# breakout.net
KiCad netlist of a schematic drawn in EAGLE
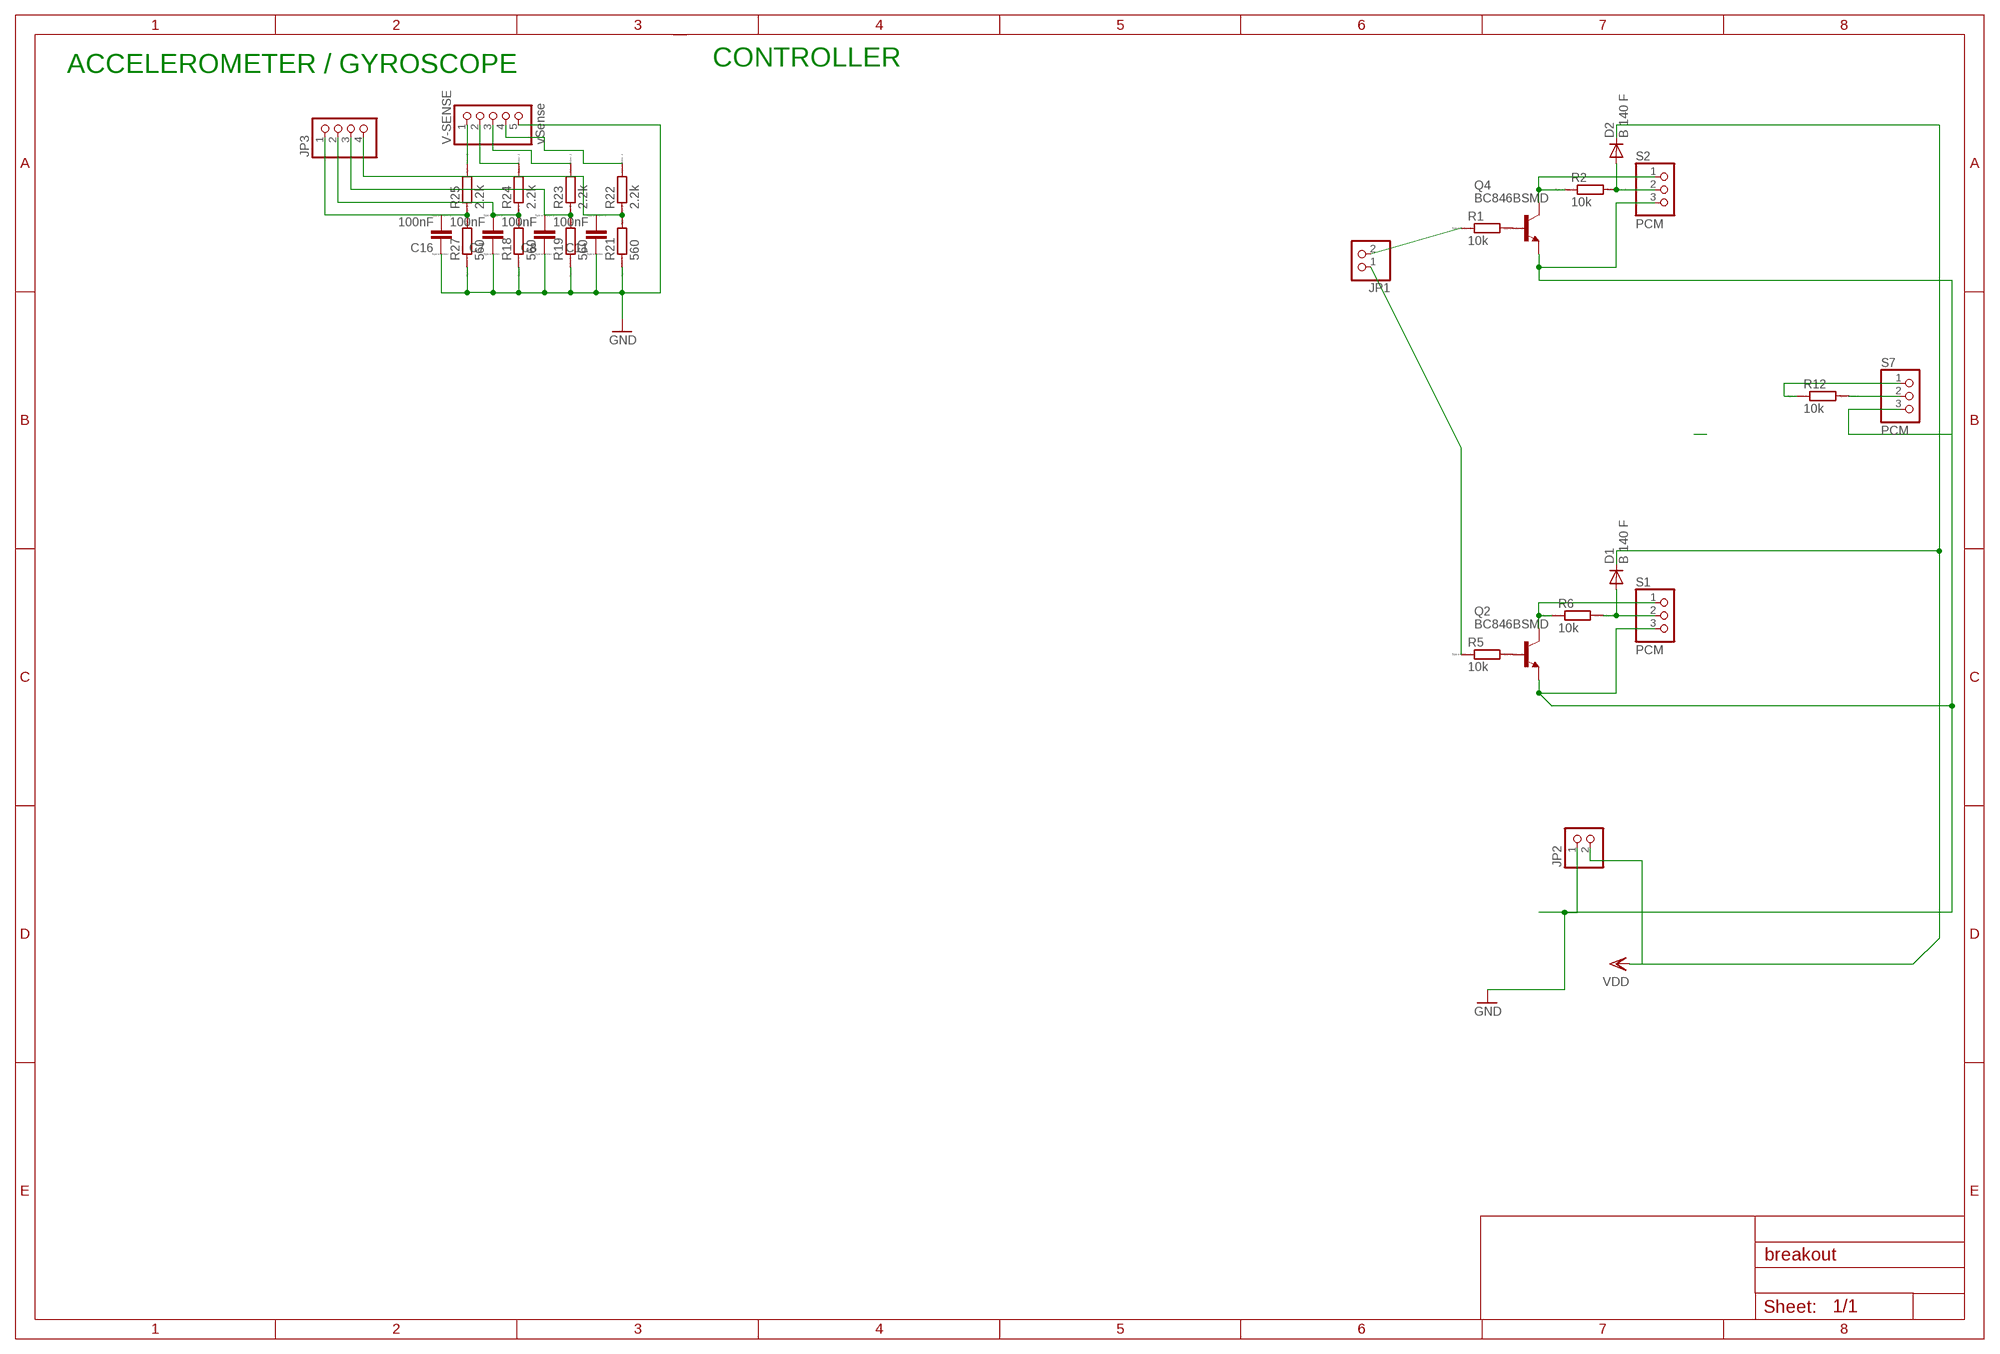
[diagram p0: schematic, sheet 1]

(export (version "E")
  (design (tool "Eeschema 10.0.6"))
  (components
    (comp (ref "C7")
      (value "100nF")
      (footprint "eagle-import:C0603")
      (libsource (lib "eagle-import") (part "CC0603"))
    )
    (comp (ref "C8")
      (value "100nF")
      (footprint "eagle-import:C0603")
      (libsource (lib "eagle-import") (part "CC0603"))
    )
    (comp (ref "C11")
      (value "100nF")
      (footprint "eagle-import:C0603")
      (libsource (lib "eagle-import") (part "CC0603"))
    )
    (comp (ref "C16")
      (value "100nF")
      (footprint "eagle-import:C0603")
      (libsource (lib "eagle-import") (part "CC0603"))
    )
    (comp (ref "D1")
      (value "B 140 F")
      (footprint "eagle-import:SOD-123_MINI-SMA")
      (libsource (lib "eagle-import") (part "CGRM400-G1"))
    )
    (comp (ref "D2")
      (value "B 140 F")
      (footprint "eagle-import:SOD-123_MINI-SMA")
      (libsource (lib "eagle-import") (part "CGRM400-G1"))
    )
    (comp (ref "JP1")
      (value "PINHD-1X2")
      (footprint "eagle-import:1X02")
      (libsource (lib "eagle-import") (part "PINHD-1X2"))
    )
    (comp (ref "JP2")
      (value "PINHD-1X2")
      (footprint "eagle-import:1X02")
      (libsource (lib "eagle-import") (part "PINHD-1X2"))
    )
    (comp (ref "JP3")
      (value "PINHD-1X4")
      (footprint "eagle-import:1X04")
      (libsource (lib "eagle-import") (part "PINHD-1X4"))
    )
    (comp (ref "Q2")
      (value "BC846BSMD")
      (footprint "eagle-import:SOT23")
      (libsource (lib "eagle-import") (part "BC846SMDB"))
    )
    (comp (ref "Q4")
      (value "BC846BSMD")
      (footprint "eagle-import:SOT23")
      (libsource (lib "eagle-import") (part "BC846SMDB"))
    )
    (comp (ref "R1")
      (value "10k")
      (footprint "eagle-import:R0603")
      (libsource (lib "eagle-import") (part "RR0603"))
    )
    (comp (ref "R2")
      (value "10k")
      (footprint "eagle-import:R0603")
      (libsource (lib "eagle-import") (part "RR0603"))
    )
    (comp (ref "R5")
      (value "10k")
      (footprint "eagle-import:R0603")
      (libsource (lib "eagle-import") (part "RR0603"))
    )
    (comp (ref "R6")
      (value "10k")
      (footprint "eagle-import:R0603")
      (libsource (lib "eagle-import") (part "RR0603"))
    )
    (comp (ref "R12")
      (value "10k")
      (footprint "eagle-import:R0603")
      (libsource (lib "eagle-import") (part "RR0603"))
    )
    (comp (ref "R18")
      (value "560")
      (footprint "eagle-import:R0603")
      (libsource (lib "eagle-import") (part "RR0603"))
    )
    (comp (ref "R19")
      (value "560")
      (footprint "eagle-import:R0603")
      (libsource (lib "eagle-import") (part "RR0603"))
    )
    (comp (ref "R21")
      (value "560")
      (footprint "eagle-import:R0603")
      (libsource (lib "eagle-import") (part "RR0603"))
    )
    (comp (ref "R22")
      (value "2.2k")
      (footprint "eagle-import:R0603")
      (libsource (lib "eagle-import") (part "RR0603"))
    )
    (comp (ref "R23")
      (value "2.2k")
      (footprint "eagle-import:R0603")
      (libsource (lib "eagle-import") (part "RR0603"))
    )
    (comp (ref "R24")
      (value "2.2k")
      (footprint "eagle-import:R0603")
      (libsource (lib "eagle-import") (part "RR0603"))
    )
    (comp (ref "R25")
      (value "2.2k")
      (footprint "eagle-import:R0603")
      (libsource (lib "eagle-import") (part "RR0603"))
    )
    (comp (ref "R27")
      (value "560")
      (footprint "eagle-import:R0603")
      (libsource (lib "eagle-import") (part "RR0603"))
    )
    (comp (ref "S1")
      (value "PCM")
      (footprint "eagle-import:1X03")
      (libsource (lib "eagle-import") (part "PINHD-1X3"))
    )
    (comp (ref "S2")
      (value "PCM")
      (footprint "eagle-import:1X03")
      (libsource (lib "eagle-import") (part "PINHD-1X3"))
    )
    (comp (ref "S7")
      (value "PCM")
      (footprint "eagle-import:1X03")
      (libsource (lib "eagle-import") (part "PINHD-1X3"))
    )
    (comp (ref "V-SENSE")
      (value "vSense")
      (footprint "eagle-import:1X05_90")
      (libsource (lib "eagle-import") (part "PINHD-1X5/90"))
    )
  )
  (nets
    (net (code "1") (name "GND") (class "Default")
      (node (ref "C11") (pin "1") (pinfunction "1_1") (pintype "passive"))
      (node (ref "C16") (pin "1") (pinfunction "1_1") (pintype "passive"))
      (node (ref "C7") (pin "1") (pinfunction "1_1") (pintype "passive"))
      (node (ref "C8") (pin "1") (pinfunction "1_1") (pintype "passive"))
      (node (ref "JP2") (pin "1") (pinfunction "1_1") (pintype "passive"))
      (node (ref "Q2") (pin "2") (pinfunction "E_2") (pintype "passive"))
      (node (ref "Q4") (pin "2") (pinfunction "E_2") (pintype "passive"))
      (node (ref "R18") (pin "1") (pinfunction "1_1") (pintype "passive"))
      (node (ref "R19") (pin "1") (pinfunction "1_1") (pintype "passive"))
      (node (ref "R21") (pin "1") (pinfunction "1_1") (pintype "passive"))
      (node (ref "R27") (pin "1") (pinfunction "1_1") (pintype "passive"))
      (node (ref "S1") (pin "3") (pinfunction "3_3") (pintype "passive"))
      (node (ref "S2") (pin "3") (pinfunction "3_3") (pintype "passive"))
      (node (ref "S7") (pin "3") (pinfunction "3_3") (pintype "passive"))
      (node (ref "V-SENSE") (pin "5") (pinfunction "5_5") (pintype "passive"))
    )
    (net (code "2") (name "Net-(C7-Pad2)") (class "Default")
      (node (ref "C7") (pin "2") (pinfunction "2_2") (pintype "passive"))
      (node (ref "JP3") (pin "2") (pinfunction "2_2") (pintype "passive"))
      (node (ref "R18") (pin "2") (pinfunction "2_2") (pintype "passive"))
      (node (ref "R24") (pin "1") (pinfunction "1_1") (pintype "passive"))
    )
    (net (code "3") (name "Net-(C8-Pad2)") (class "Default")
      (node (ref "C8") (pin "2") (pinfunction "2_2") (pintype "passive"))
      (node (ref "JP3") (pin "3") (pinfunction "3_3") (pintype "passive"))
      (node (ref "R19") (pin "2") (pinfunction "2_2") (pintype "passive"))
      (node (ref "R23") (pin "1") (pinfunction "1_1") (pintype "passive"))
    )
    (net (code "4") (name "Net-(C11-Pad2)") (class "Default")
      (node (ref "C11") (pin "2") (pinfunction "2_2") (pintype "passive"))
      (node (ref "JP3") (pin "4") (pinfunction "4_4") (pintype "passive"))
      (node (ref "R21") (pin "2") (pinfunction "2_2") (pintype "passive"))
      (node (ref "R22") (pin "1") (pinfunction "1_1") (pintype "passive"))
    )
    (net (code "5") (name "Net-(C16-Pad2)") (class "Default")
      (node (ref "C16") (pin "2") (pinfunction "2_2") (pintype "passive"))
      (node (ref "JP3") (pin "1") (pinfunction "1_1") (pintype "passive"))
      (node (ref "R25") (pin "1") (pinfunction "1_1") (pintype "passive"))
      (node (ref "R27") (pin "2") (pinfunction "2_2") (pintype "passive"))
    )
    (net (code "6") (name "Net-(D1-PadA)") (class "Default")
      (node (ref "D1") (pin "A") (pinfunction "A_A") (pintype "passive"))
      (node (ref "R6") (pin "2") (pinfunction "2_2") (pintype "passive"))
      (node (ref "S1") (pin "2") (pinfunction "2_2") (pintype "passive"))
    )
    (net (code "7") (name "Net-(D2-PadA)") (class "Default")
      (node (ref "D2") (pin "A") (pinfunction "A_A") (pintype "passive"))
      (node (ref "R2") (pin "2") (pinfunction "2_2") (pintype "passive"))
      (node (ref "S2") (pin "2") (pinfunction "2_2") (pintype "passive"))
    )
    (net (code "8") (name "Net-(JP1-Pad1)") (class "Default")
      (node (ref "JP1") (pin "1") (pinfunction "1_1") (pintype "passive"))
      (node (ref "R5") (pin "1") (pinfunction "1_1") (pintype "passive"))
    )
    (net (code "9") (name "Net-(JP1-Pad2)") (class "Default")
      (node (ref "JP1") (pin "2") (pinfunction "2_2") (pintype "passive"))
      (node (ref "R1") (pin "1") (pinfunction "1_1") (pintype "passive"))
    )
    (net (code "10") (name "Net-(Q2-B)") (class "Default")
      (node (ref "Q2") (pin "1") (pinfunction "B_1") (pintype "passive"))
      (node (ref "R5") (pin "2") (pinfunction "2_2") (pintype "passive"))
    )
    (net (code "11") (name "Net-(Q2-C)") (class "Default")
      (node (ref "Q2") (pin "3") (pinfunction "C_3") (pintype "passive"))
      (node (ref "R6") (pin "1") (pinfunction "1_1") (pintype "passive"))
      (node (ref "S1") (pin "1") (pinfunction "1_1") (pintype "passive"))
    )
    (net (code "12") (name "Net-(Q4-B)") (class "Default")
      (node (ref "Q4") (pin "1") (pinfunction "B_1") (pintype "passive"))
      (node (ref "R1") (pin "2") (pinfunction "2_2") (pintype "passive"))
    )
    (net (code "13") (name "Net-(Q4-C)") (class "Default")
      (node (ref "Q4") (pin "3") (pinfunction "C_3") (pintype "passive"))
      (node (ref "R2") (pin "1") (pinfunction "1_1") (pintype "passive"))
      (node (ref "S2") (pin "1") (pinfunction "1_1") (pintype "passive"))
    )
    (net (code "14") (name "Net-(R12-Pad1)") (class "Default")
      (node (ref "R12") (pin "1") (pinfunction "1_1") (pintype "passive"))
      (node (ref "S7") (pin "1") (pinfunction "1_1") (pintype "passive"))
    )
    (net (code "15") (name "Net-(R12-Pad2)") (class "Default")
      (node (ref "R12") (pin "2") (pinfunction "2_2") (pintype "passive"))
      (node (ref "S7") (pin "2") (pinfunction "2_2") (pintype "passive"))
    )
    (net (code "16") (name "Net-(R22-Pad2)") (class "Default")
      (node (ref "R22") (pin "2") (pinfunction "2_2") (pintype "passive"))
      (node (ref "V-SENSE") (pin "4") (pinfunction "4_4") (pintype "passive"))
    )
    (net (code "17") (name "Net-(R23-Pad2)") (class "Default")
      (node (ref "R23") (pin "2") (pinfunction "2_2") (pintype "passive"))
      (node (ref "V-SENSE") (pin "3") (pinfunction "3_3") (pintype "passive"))
    )
    (net (code "18") (name "Net-(R24-Pad2)") (class "Default")
      (node (ref "R24") (pin "2") (pinfunction "2_2") (pintype "passive"))
      (node (ref "V-SENSE") (pin "2") (pinfunction "2_2") (pintype "passive"))
    )
    (net (code "19") (name "Net-(R25-Pad2)") (class "Default")
      (node (ref "R25") (pin "2") (pinfunction "2_2") (pintype "passive"))
      (node (ref "V-SENSE") (pin "1") (pinfunction "1_1") (pintype "passive"))
    )
    (net (code "20") (name "VDD") (class "Default")
      (node (ref "D1") (pin "C") (pinfunction "C_C") (pintype "passive"))
      (node (ref "D2") (pin "C") (pinfunction "C_C") (pintype "passive"))
      (node (ref "JP2") (pin "2") (pinfunction "2_2") (pintype "passive"))
    )
  )
)
